# TreeV1Part2.net
KiCad netlist of a schematic drawn in EAGLE
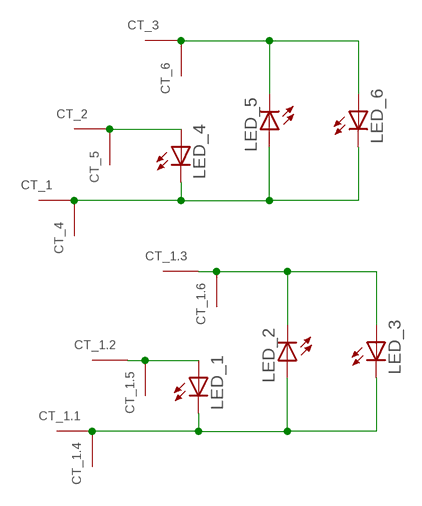
[diagram p0: schematic, sheet 1]

(export (version "E")
  (design (tool "Eeschema 10.0.6"))
  (components
    (comp (ref "CT_1")
      (value "SMD_PAD_SINGLE")
      (footprint "eagle-import:5X5TREEPAD_SINGLE")
      (libsource (lib "eagle-import") (part "SMD_PAD_SINGLE"))
    )
    (comp (ref "CT_1.1")
      (value "SMD_PAD_SINGLE")
      (footprint "eagle-import:5X5TREEPAD_SINGLE")
      (libsource (lib "eagle-import") (part "SMD_PAD_SINGLE"))
    )
    (comp (ref "CT_1.2")
      (value "SMD_PAD_SINGLE")
      (footprint "eagle-import:5X5TREEPAD_SINGLE")
      (libsource (lib "eagle-import") (part "SMD_PAD_SINGLE"))
    )
    (comp (ref "CT_1.3")
      (value "SMD_PAD_SINGLE")
      (footprint "eagle-import:5X5TREEPAD_SINGLE")
      (libsource (lib "eagle-import") (part "SMD_PAD_SINGLE"))
    )
    (comp (ref "CT_1.4")
      (value "SMD_PAD_SINGLE")
      (footprint "eagle-import:5X5TREEPAD_SINGLE")
      (libsource (lib "eagle-import") (part "SMD_PAD_SINGLE"))
    )
    (comp (ref "CT_1.5")
      (value "SMD_PAD_SINGLE")
      (footprint "eagle-import:5X5TREEPAD_SINGLE")
      (libsource (lib "eagle-import") (part "SMD_PAD_SINGLE"))
    )
    (comp (ref "CT_1.6")
      (value "SMD_PAD_SINGLE")
      (footprint "eagle-import:5X5TREEPAD_SINGLE")
      (libsource (lib "eagle-import") (part "SMD_PAD_SINGLE"))
    )
    (comp (ref "CT_2")
      (value "SMD_PAD_SINGLE")
      (footprint "eagle-import:5X5TREEPAD_SINGLE")
      (libsource (lib "eagle-import") (part "SMD_PAD_SINGLE"))
    )
    (comp (ref "CT_3")
      (value "SMD_PAD_SINGLE")
      (footprint "eagle-import:5X5TREEPAD_SINGLE")
      (libsource (lib "eagle-import") (part "SMD_PAD_SINGLE"))
    )
    (comp (ref "CT_4")
      (value "SMD_PAD_SINGLE")
      (footprint "eagle-import:5X5TREEPAD_SINGLE")
      (libsource (lib "eagle-import") (part "SMD_PAD_SINGLE"))
    )
    (comp (ref "CT_5")
      (value "SMD_PAD_SINGLE")
      (footprint "eagle-import:5X5TREEPAD_SINGLE")
      (libsource (lib "eagle-import") (part "SMD_PAD_SINGLE"))
    )
    (comp (ref "CT_6")
      (value "SMD_PAD_SINGLE")
      (footprint "eagle-import:5X5TREEPAD_SINGLE")
      (libsource (lib "eagle-import") (part "SMD_PAD_SINGLE"))
    )
    (comp (ref "LED_1")
      (value "LEDLED_CLEAN_EDGE")
      (footprint "eagle-import:1X02_NO_SILK")
      (libsource (lib "eagle-import") (part "LEDLED_CLEAN_EDGE"))
    )
    (comp (ref "LED_2")
      (value "LEDLED_CLEAN_EDGE")
      (footprint "eagle-import:1X02_NO_SILK")
      (libsource (lib "eagle-import") (part "LEDLED_CLEAN_EDGE"))
    )
    (comp (ref "LED_3")
      (value "LEDLED_CLEAN_EDGE")
      (footprint "eagle-import:1X02_NO_SILK")
      (libsource (lib "eagle-import") (part "LEDLED_CLEAN_EDGE"))
    )
    (comp (ref "LED_4")
      (value "LEDLED_CLEAN_EDGE")
      (footprint "eagle-import:1X02_NO_SILK")
      (libsource (lib "eagle-import") (part "LEDLED_CLEAN_EDGE"))
    )
    (comp (ref "LED_5")
      (value "LEDLED_CLEAN_EDGE")
      (footprint "eagle-import:1X02_NO_SILK")
      (libsource (lib "eagle-import") (part "LEDLED_CLEAN_EDGE"))
    )
    (comp (ref "LED_6")
      (value "LEDLED_CLEAN_EDGE")
      (footprint "eagle-import:1X02_NO_SILK")
      (libsource (lib "eagle-import") (part "LEDLED_CLEAN_EDGE"))
    )
  )
  (nets
    (net (code "1") (name "Net-(LED_1-A)") (class "Default")
      (node (ref "CT_1.2") (pin "P$1") (pinfunction "P$1_P$1") (pintype "bidirectional"))
      (node (ref "CT_1.5") (pin "P$1") (pinfunction "P$1_P$1") (pintype "bidirectional"))
      (node (ref "LED_1") (pin "1") (pinfunction "A_1") (pintype "passive"))
    )
    (net (code "2") (name "Net-(LED_1-C)") (class "Default")
      (node (ref "CT_1.1") (pin "P$1") (pinfunction "P$1_P$1") (pintype "bidirectional"))
      (node (ref "CT_1.4") (pin "P$1") (pinfunction "P$1_P$1") (pintype "bidirectional"))
      (node (ref "LED_1") (pin "2") (pinfunction "C_2") (pintype "passive"))
      (node (ref "LED_2") (pin "1") (pinfunction "A_1") (pintype "passive"))
      (node (ref "LED_3") (pin "2") (pinfunction "C_2") (pintype "passive"))
    )
    (net (code "3") (name "Net-(LED_2-C)") (class "Default")
      (node (ref "CT_1.3") (pin "P$1") (pinfunction "P$1_P$1") (pintype "bidirectional"))
      (node (ref "CT_1.6") (pin "P$1") (pinfunction "P$1_P$1") (pintype "bidirectional"))
      (node (ref "LED_2") (pin "2") (pinfunction "C_2") (pintype "passive"))
      (node (ref "LED_3") (pin "1") (pinfunction "A_1") (pintype "passive"))
    )
    (net (code "4") (name "Net-(LED_4-A)") (class "Default")
      (node (ref "CT_2") (pin "P$1") (pinfunction "P$1_P$1") (pintype "bidirectional"))
      (node (ref "CT_5") (pin "P$1") (pinfunction "P$1_P$1") (pintype "bidirectional"))
      (node (ref "LED_4") (pin "1") (pinfunction "A_1") (pintype "passive"))
    )
    (net (code "5") (name "Net-(LED_4-C)") (class "Default")
      (node (ref "CT_1") (pin "P$1") (pinfunction "P$1_P$1") (pintype "bidirectional"))
      (node (ref "CT_4") (pin "P$1") (pinfunction "P$1_P$1") (pintype "bidirectional"))
      (node (ref "LED_4") (pin "2") (pinfunction "C_2") (pintype "passive"))
      (node (ref "LED_5") (pin "1") (pinfunction "A_1") (pintype "passive"))
      (node (ref "LED_6") (pin "2") (pinfunction "C_2") (pintype "passive"))
    )
    (net (code "6") (name "Net-(LED_5-C)") (class "Default")
      (node (ref "CT_3") (pin "P$1") (pinfunction "P$1_P$1") (pintype "bidirectional"))
      (node (ref "CT_6") (pin "P$1") (pinfunction "P$1_P$1") (pintype "bidirectional"))
      (node (ref "LED_5") (pin "2") (pinfunction "C_2") (pintype "passive"))
      (node (ref "LED_6") (pin "1") (pinfunction "A_1") (pintype "passive"))
    )
  )
)
